# SCH_ESP-Mar_2024-04-21.net
KiCad netlist of a schematic drawn in EasyEDA
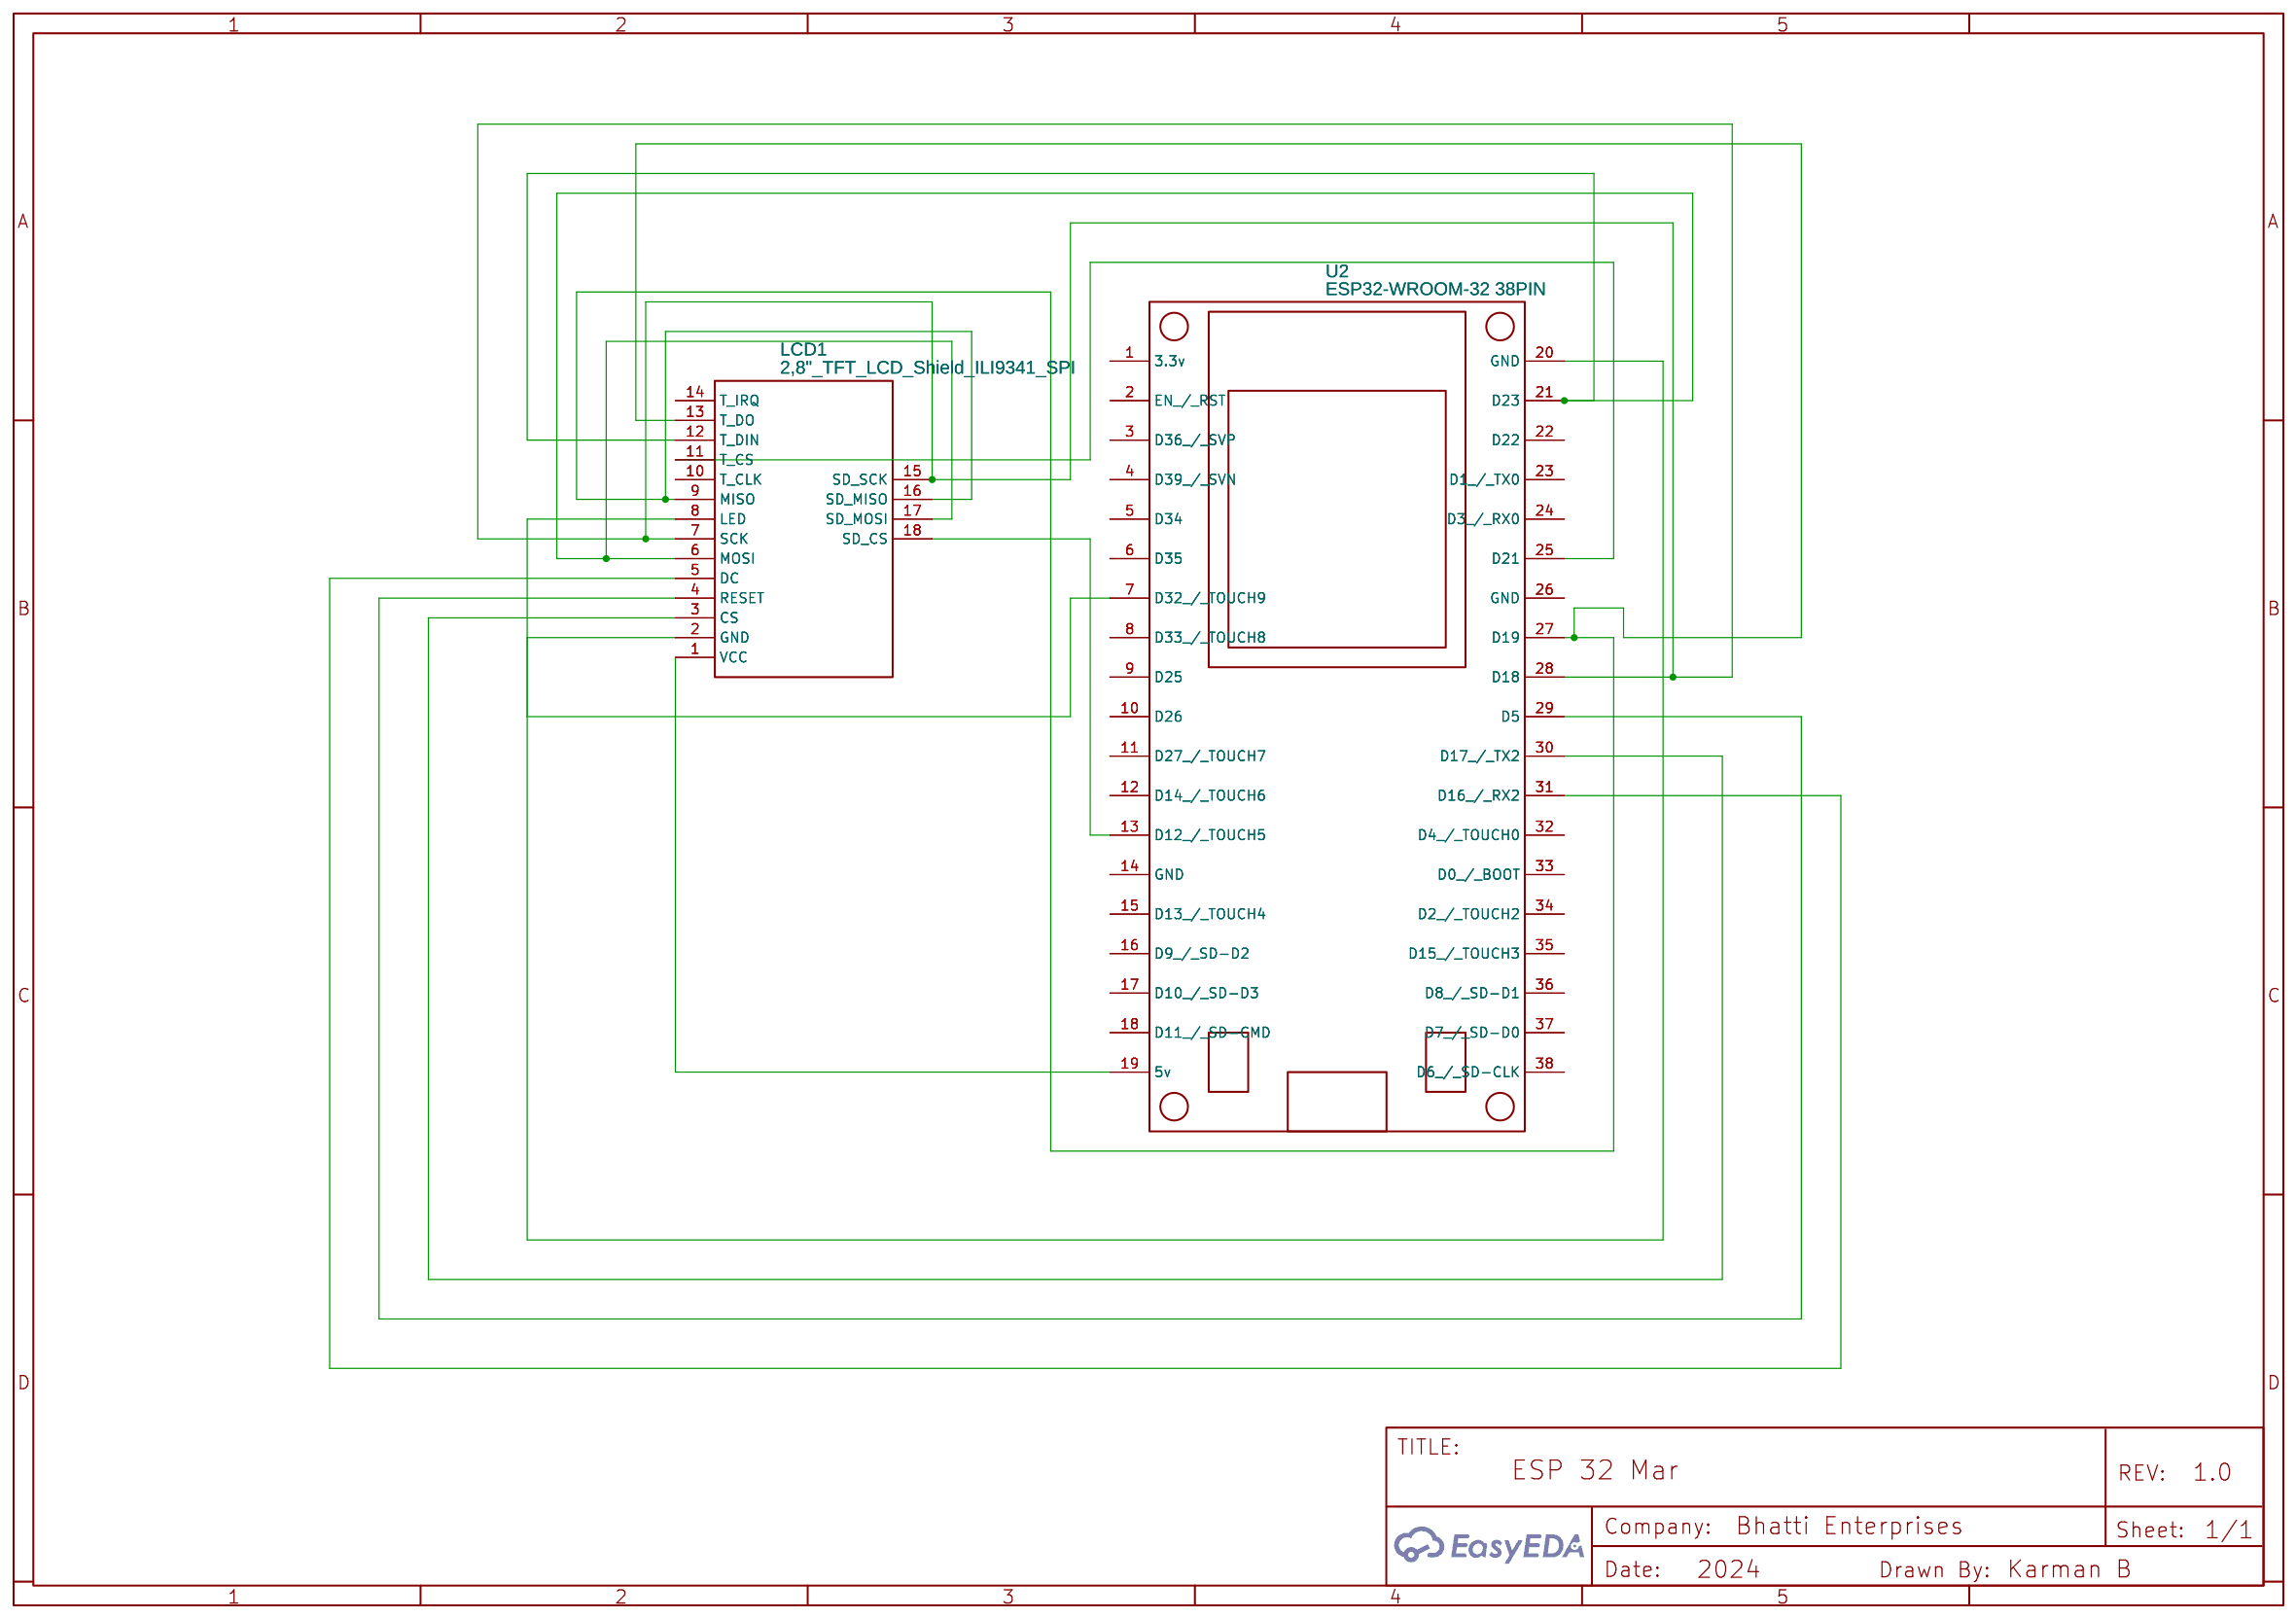
[diagram p0: Sheet_1]
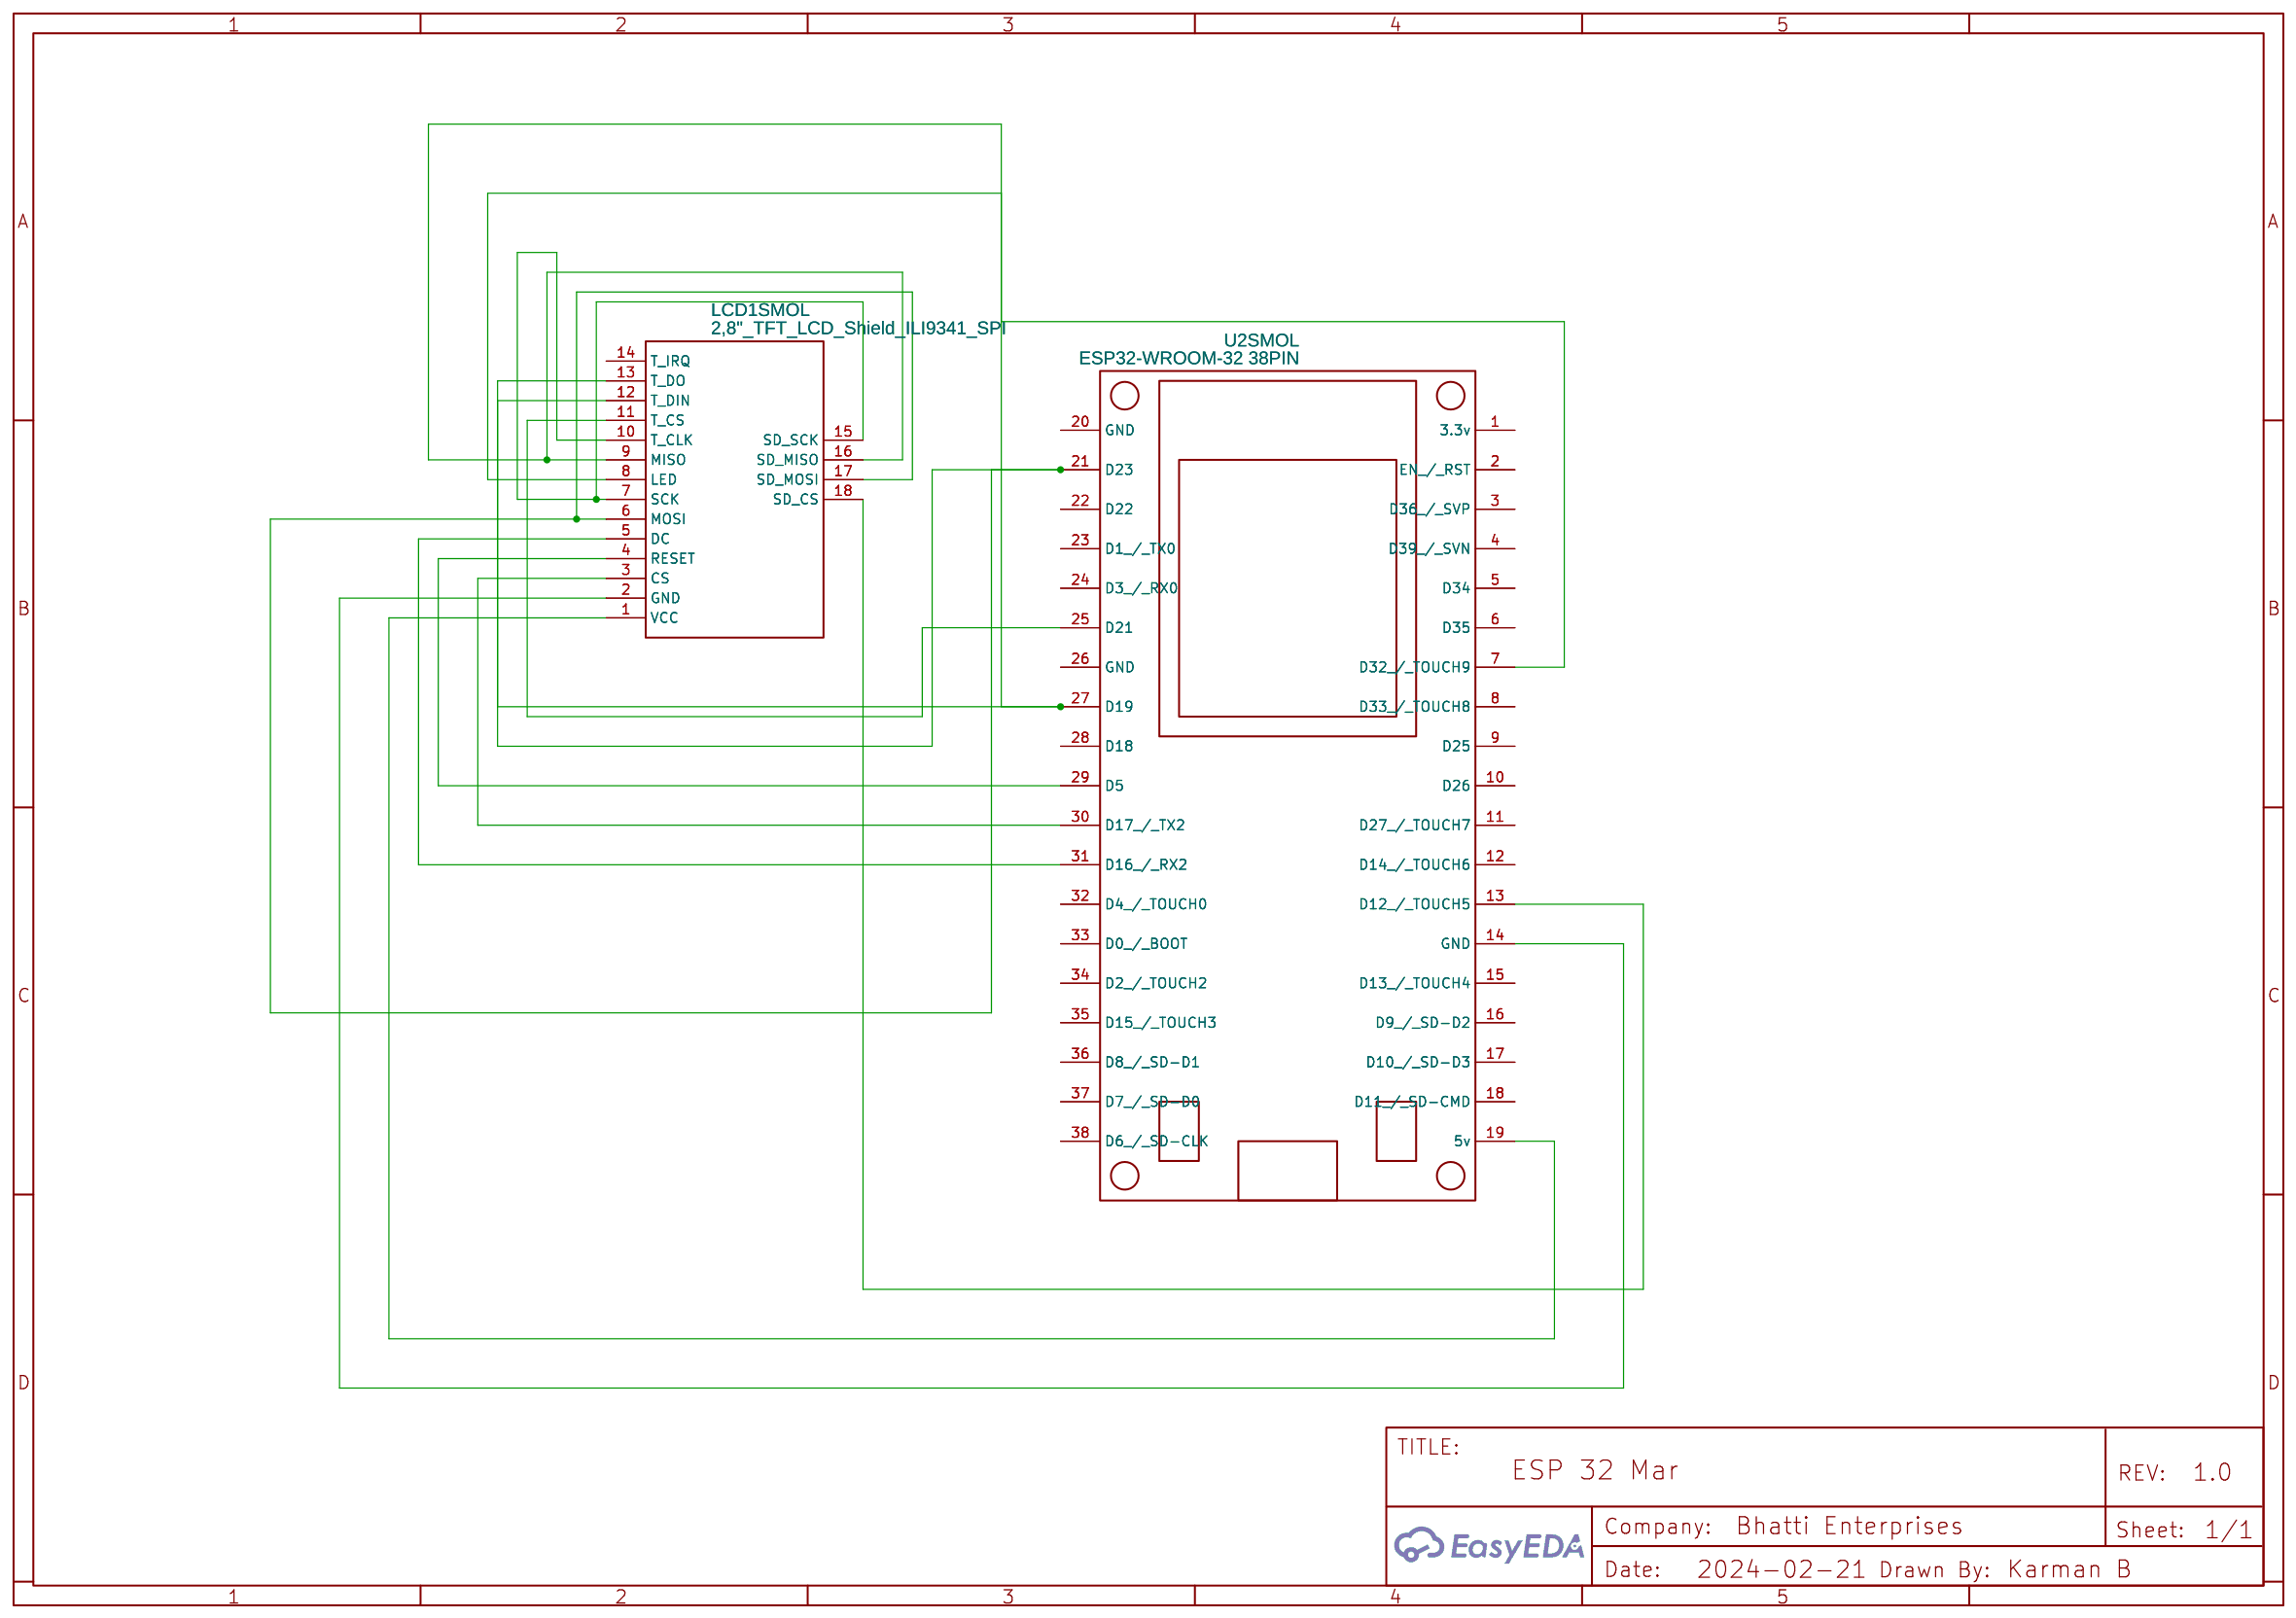
[diagram p1: Sheet SMOL]

(export (version "E")
  (design (tool "Eeschema 10.0.6"))
  (components
    (comp (ref "LCD1")
      (value "2,8\"_TFT_LCD_Shield_ILI9341_SPI")
      (libsource (lib "") (part "2,8{dblquote}_TFT_LCD_Shield_ILI9341_SPI"))
    )
    (comp (ref "U2")
      (value "ESP32-WROOM-32 38PIN")
      (fields (field (name "Manufacturer Part") "ESP32 Development Board"))
      (libsource (lib "") (part "ESP32-WROOM-32 38PIN"))
    )
    (comp (ref "LCD1SMOL")
      (value "2,8\"_TFT_LCD_Shield_ILI9341_SPI")
      (libsource (lib "") (part "2,8{dblquote}_TFT_LCD_Shield_ILI9341_SPI"))
    )
    (comp (ref "U2SMOL")
      (value "ESP32-WROOM-32 38PIN")
      (fields (field (name "Manufacturer Part") "ESP32 Development Board"))
      (libsource (lib "") (part "ESP32-WROOM-32 38PIN"))
    )
  )
  (nets
    (net (code "1") (name "Net-(LCD1-CS)") (class "Default")
      (node (ref "LCD1") (pin "3") (pinfunction "CS_3") (pintype "unspecified"))
      (node (ref "U2") (pin "30") (pinfunction "D17_/_TX2_30") (pintype "bidirectional"))
    )
    (net (code "2") (name "Net-(LCD1-DC)") (class "Default")
      (node (ref "LCD1") (pin "5") (pinfunction "DC_5") (pintype "unspecified"))
      (node (ref "U2") (pin "31") (pinfunction "D16_/_RX2_31") (pintype "bidirectional"))
    )
    (net (code "3") (name "Net-(LCD1-GND)") (class "Default")
      (node (ref "LCD1") (pin "2") (pinfunction "GND_2") (pintype "unspecified"))
      (node (ref "U2") (pin "20") (pinfunction "GND_20") (pintype "passive"))
    )
    (net (code "4") (name "Net-(LCD1-LED)") (class "Default")
      (node (ref "LCD1") (pin "8") (pinfunction "LED_8") (pintype "unspecified"))
      (node (ref "U2") (pin "7") (pinfunction "D32_/_TOUCH9_7") (pintype "bidirectional"))
    )
    (net (code "5") (name "Net-(LCD1-MISO)") (class "Default")
      (node (ref "LCD1") (pin "13") (pinfunction "T_DO_13") (pintype "unspecified"))
      (node (ref "LCD1") (pin "16") (pinfunction "SD_MISO_16") (pintype "unspecified"))
      (node (ref "LCD1") (pin "9") (pinfunction "MISO_9") (pintype "unspecified"))
      (node (ref "U2") (pin "27") (pinfunction "D19_27") (pintype "bidirectional"))
    )
    (net (code "6") (name "Net-(LCD1-MOSI)") (class "Default")
      (node (ref "LCD1") (pin "12") (pinfunction "T_DIN_12") (pintype "unspecified"))
      (node (ref "LCD1") (pin "17") (pinfunction "SD_MOSI_17") (pintype "unspecified"))
      (node (ref "LCD1") (pin "6") (pinfunction "MOSI_6") (pintype "unspecified"))
      (node (ref "U2") (pin "21") (pinfunction "D23_21") (pintype "bidirectional"))
    )
    (net (code "7") (name "Net-(LCD1-RESET)") (class "Default")
      (node (ref "LCD1") (pin "4") (pinfunction "RESET_4") (pintype "unspecified"))
      (node (ref "U2") (pin "29") (pinfunction "D5_29") (pintype "bidirectional"))
    )
    (net (code "8") (name "Net-(LCD1-SCK)") (class "Default")
      (node (ref "LCD1") (pin "15") (pinfunction "SD_SCK_15") (pintype "unspecified"))
      (node (ref "LCD1") (pin "7") (pinfunction "SCK_7") (pintype "unspecified"))
      (node (ref "U2") (pin "28") (pinfunction "D18_28") (pintype "bidirectional"))
    )
    (net (code "9") (name "Net-(LCD1-SD_CS)") (class "Default")
      (node (ref "LCD1") (pin "18") (pinfunction "SD_CS_18") (pintype "unspecified"))
      (node (ref "U2") (pin "13") (pinfunction "D12_/_TOUCH5_13") (pintype "bidirectional"))
    )
    (net (code "10") (name "Net-(LCD1-T_CS)") (class "Default")
      (node (ref "LCD1") (pin "11") (pinfunction "T_CS_11") (pintype "unspecified"))
      (node (ref "U2") (pin "25") (pinfunction "D21_25") (pintype "bidirectional"))
    )
    (net (code "11") (name "Net-(LCD1-VCC)") (class "Default")
      (node (ref "LCD1") (pin "1") (pinfunction "VCC_1") (pintype "unspecified"))
      (node (ref "U2") (pin "19") (pinfunction "5v_19") (pintype "passive"))
    )
    (net (code "12") (name "Net-(LCD1SMOL-CS)") (class "Default")
      (node (ref "LCD1SMOL") (pin "3") (pinfunction "CS_3") (pintype "unspecified"))
      (node (ref "U2SMOL") (pin "30") (pinfunction "D17_/_TX2_30") (pintype "bidirectional"))
    )
    (net (code "13") (name "Net-(LCD1SMOL-DC)") (class "Default")
      (node (ref "LCD1SMOL") (pin "5") (pinfunction "DC_5") (pintype "unspecified"))
      (node (ref "U2SMOL") (pin "31") (pinfunction "D16_/_RX2_31") (pintype "bidirectional"))
    )
    (net (code "14") (name "Net-(LCD1SMOL-GND)") (class "Default")
      (node (ref "LCD1SMOL") (pin "2") (pinfunction "GND_2") (pintype "unspecified"))
      (node (ref "U2SMOL") (pin "14") (pinfunction "GND_14") (pintype "passive"))
    )
    (net (code "15") (name "Net-(LCD1SMOL-LED)") (class "Default")
      (node (ref "LCD1SMOL") (pin "8") (pinfunction "LED_8") (pintype "unspecified"))
      (node (ref "U2SMOL") (pin "7") (pinfunction "D32_/_TOUCH9_7") (pintype "bidirectional"))
    )
    (net (code "16") (name "Net-(LCD1SMOL-MISO)") (class "Default")
      (node (ref "LCD1SMOL") (pin "13") (pinfunction "T_DO_13") (pintype "unspecified"))
      (node (ref "LCD1SMOL") (pin "16") (pinfunction "SD_MISO_16") (pintype "unspecified"))
      (node (ref "LCD1SMOL") (pin "9") (pinfunction "MISO_9") (pintype "unspecified"))
      (node (ref "U2SMOL") (pin "27") (pinfunction "D19_27") (pintype "bidirectional"))
    )
    (net (code "17") (name "Net-(LCD1SMOL-MOSI)") (class "Default")
      (node (ref "LCD1SMOL") (pin "12") (pinfunction "T_DIN_12") (pintype "unspecified"))
      (node (ref "LCD1SMOL") (pin "17") (pinfunction "SD_MOSI_17") (pintype "unspecified"))
      (node (ref "LCD1SMOL") (pin "6") (pinfunction "MOSI_6") (pintype "unspecified"))
      (node (ref "U2SMOL") (pin "21") (pinfunction "D23_21") (pintype "bidirectional"))
    )
    (net (code "18") (name "Net-(LCD1SMOL-RESET)") (class "Default")
      (node (ref "LCD1SMOL") (pin "4") (pinfunction "RESET_4") (pintype "unspecified"))
      (node (ref "U2SMOL") (pin "29") (pinfunction "D5_29") (pintype "bidirectional"))
    )
    (net (code "19") (name "Net-(LCD1SMOL-SCK)") (class "Default")
      (node (ref "LCD1SMOL") (pin "10") (pinfunction "T_CLK_10") (pintype "unspecified"))
      (node (ref "LCD1SMOL") (pin "15") (pinfunction "SD_SCK_15") (pintype "unspecified"))
      (node (ref "LCD1SMOL") (pin "7") (pinfunction "SCK_7") (pintype "unspecified"))
    )
    (net (code "20") (name "Net-(LCD1SMOL-SD_CS)") (class "Default")
      (node (ref "LCD1SMOL") (pin "18") (pinfunction "SD_CS_18") (pintype "unspecified"))
      (node (ref "U2SMOL") (pin "13") (pinfunction "D12_/_TOUCH5_13") (pintype "bidirectional"))
    )
    (net (code "21") (name "Net-(LCD1SMOL-T_CS)") (class "Default")
      (node (ref "LCD1SMOL") (pin "11") (pinfunction "T_CS_11") (pintype "unspecified"))
      (node (ref "U2SMOL") (pin "25") (pinfunction "D21_25") (pintype "bidirectional"))
    )
    (net (code "22") (name "Net-(LCD1SMOL-VCC)") (class "Default")
      (node (ref "LCD1SMOL") (pin "1") (pinfunction "VCC_1") (pintype "unspecified"))
      (node (ref "U2SMOL") (pin "19") (pinfunction "5v_19") (pintype "passive"))
    )
    (net (code "23") (name "unconnected-(LCD1-T_CLK-Pad10)") (class "Default")
      (node (ref "LCD1") (pin "10") (pinfunction "T_CLK_10") (pintype "unspecified"))
    )
    (net (code "24") (name "unconnected-(LCD1-T_IRQ-Pad14)") (class "Default")
      (node (ref "LCD1") (pin "14") (pinfunction "T_IRQ_14") (pintype "unspecified"))
    )
    (net (code "25") (name "unconnected-(LCD1SMOL-T_IRQ-Pad14)") (class "Default")
      (node (ref "LCD1SMOL") (pin "14") (pinfunction "T_IRQ_14") (pintype "unspecified"))
    )
    (net (code "26") (name "unconnected-(U2-3.3v-Pad1)") (class "Default")
      (node (ref "U2") (pin "1") (pinfunction "3.3v_1") (pintype "passive"))
    )
    (net (code "27") (name "unconnected-(U2-D0_{slash}_BOOT-Pad33)") (class "Default")
      (node (ref "U2") (pin "33") (pinfunction "D0_/_BOOT_33") (pintype "bidirectional"))
    )
    (net (code "28") (name "unconnected-(U2-D1_{slash}_TX0-Pad23)") (class "Default")
      (node (ref "U2") (pin "23") (pinfunction "D1_/_TX0_23") (pintype "bidirectional"))
    )
    (net (code "29") (name "unconnected-(U2-D2_{slash}_TOUCH2-Pad34)") (class "Default")
      (node (ref "U2") (pin "34") (pinfunction "D2_/_TOUCH2_34") (pintype "bidirectional"))
    )
    (net (code "30") (name "unconnected-(U2-D3_{slash}_RX0-Pad24)") (class "Default")
      (node (ref "U2") (pin "24") (pinfunction "D3_/_RX0_24") (pintype "bidirectional"))
    )
    (net (code "31") (name "unconnected-(U2-D4_{slash}_TOUCH0-Pad32)") (class "Default")
      (node (ref "U2") (pin "32") (pinfunction "D4_/_TOUCH0_32") (pintype "bidirectional"))
    )
    (net (code "32") (name "unconnected-(U2-D6_{slash}_SD-CLK-Pad38)") (class "Default")
      (node (ref "U2") (pin "38") (pinfunction "D6_/_SD-CLK_38") (pintype "bidirectional"))
    )
    (net (code "33") (name "unconnected-(U2-D7_{slash}_SD-D0-Pad37)") (class "Default")
      (node (ref "U2") (pin "37") (pinfunction "D7_/_SD-D0_37") (pintype "bidirectional"))
    )
    (net (code "34") (name "unconnected-(U2-D8_{slash}_SD-D1-Pad36)") (class "Default")
      (node (ref "U2") (pin "36") (pinfunction "D8_/_SD-D1_36") (pintype "bidirectional"))
    )
    (net (code "35") (name "unconnected-(U2-D9_{slash}_SD-D2-Pad16)") (class "Default")
      (node (ref "U2") (pin "16") (pinfunction "D9_/_SD-D2_16") (pintype "bidirectional"))
    )
    (net (code "36") (name "unconnected-(U2-D10_{slash}_SD-D3-Pad17)") (class "Default")
      (node (ref "U2") (pin "17") (pinfunction "D10_/_SD-D3_17") (pintype "bidirectional"))
    )
    (net (code "37") (name "unconnected-(U2-D11_{slash}_SD-CMD-Pad18)") (class "Default")
      (node (ref "U2") (pin "18") (pinfunction "D11_/_SD-CMD_18") (pintype "bidirectional"))
    )
    (net (code "38") (name "unconnected-(U2-D13_{slash}_TOUCH4-Pad15)") (class "Default")
      (node (ref "U2") (pin "15") (pinfunction "D13_/_TOUCH4_15") (pintype "bidirectional"))
    )
    (net (code "39") (name "unconnected-(U2-D14_{slash}_TOUCH6-Pad12)") (class "Default")
      (node (ref "U2") (pin "12") (pinfunction "D14_/_TOUCH6_12") (pintype "bidirectional"))
    )
    (net (code "40") (name "unconnected-(U2-D15_{slash}_TOUCH3-Pad35)") (class "Default")
      (node (ref "U2") (pin "35") (pinfunction "D15_/_TOUCH3_35") (pintype "bidirectional"))
    )
    (net (code "41") (name "unconnected-(U2-D22-Pad22)") (class "Default")
      (node (ref "U2") (pin "22") (pinfunction "D22_22") (pintype "bidirectional"))
    )
    (net (code "42") (name "unconnected-(U2-D25-Pad9)") (class "Default")
      (node (ref "U2") (pin "9") (pinfunction "D25_9") (pintype "bidirectional"))
    )
    (net (code "43") (name "unconnected-(U2-D26-Pad10)") (class "Default")
      (node (ref "U2") (pin "10") (pinfunction "D26_10") (pintype "bidirectional"))
    )
    (net (code "44") (name "unconnected-(U2-D27_{slash}_TOUCH7-Pad11)") (class "Default")
      (node (ref "U2") (pin "11") (pinfunction "D27_/_TOUCH7_11") (pintype "bidirectional"))
    )
    (net (code "45") (name "unconnected-(U2-D33_{slash}_TOUCH8-Pad8)") (class "Default")
      (node (ref "U2") (pin "8") (pinfunction "D33_/_TOUCH8_8") (pintype "bidirectional"))
    )
    (net (code "46") (name "unconnected-(U2-D34-Pad5)") (class "Default")
      (node (ref "U2") (pin "5") (pinfunction "D34_5") (pintype "bidirectional"))
    )
    (net (code "47") (name "unconnected-(U2-D35-Pad6)") (class "Default")
      (node (ref "U2") (pin "6") (pinfunction "D35_6") (pintype "bidirectional"))
    )
    (net (code "48") (name "unconnected-(U2-D36_{slash}_SVP-Pad3)") (class "Default")
      (node (ref "U2") (pin "3") (pinfunction "D36_/_SVP_3") (pintype "bidirectional"))
    )
    (net (code "49") (name "unconnected-(U2-D39_{slash}_SVN-Pad4)") (class "Default")
      (node (ref "U2") (pin "4") (pinfunction "D39_/_SVN_4") (pintype "bidirectional"))
    )
    (net (code "50") (name "unconnected-(U2-EN_{slash}_RST-Pad2)") (class "Default")
      (node (ref "U2") (pin "2") (pinfunction "EN_/_RST_2") (pintype "bidirectional"))
    )
    (net (code "51") (name "unconnected-(U2-GND-Pad14)") (class "Default")
      (node (ref "U2") (pin "14") (pinfunction "GND_14") (pintype "passive"))
    )
    (net (code "52") (name "unconnected-(U2-GND-Pad26)") (class "Default")
      (node (ref "U2") (pin "26") (pinfunction "GND_26") (pintype "passive"))
    )
    (net (code "53") (name "unconnected-(U2SMOL-3.3v-Pad1)") (class "Default")
      (node (ref "U2SMOL") (pin "1") (pinfunction "3.3v_1") (pintype "passive"))
    )
    (net (code "54") (name "unconnected-(U2SMOL-D0_{slash}_BOOT-Pad33)") (class "Default")
      (node (ref "U2SMOL") (pin "33") (pinfunction "D0_/_BOOT_33") (pintype "bidirectional"))
    )
    (net (code "55") (name "unconnected-(U2SMOL-D1_{slash}_TX0-Pad23)") (class "Default")
      (node (ref "U2SMOL") (pin "23") (pinfunction "D1_/_TX0_23") (pintype "bidirectional"))
    )
    (net (code "56") (name "unconnected-(U2SMOL-D2_{slash}_TOUCH2-Pad34)") (class "Default")
      (node (ref "U2SMOL") (pin "34") (pinfunction "D2_/_TOUCH2_34") (pintype "bidirectional"))
    )
    (net (code "57") (name "unconnected-(U2SMOL-D3_{slash}_RX0-Pad24)") (class "Default")
      (node (ref "U2SMOL") (pin "24") (pinfunction "D3_/_RX0_24") (pintype "bidirectional"))
    )
    (net (code "58") (name "unconnected-(U2SMOL-D4_{slash}_TOUCH0-Pad32)") (class "Default")
      (node (ref "U2SMOL") (pin "32") (pinfunction "D4_/_TOUCH0_32") (pintype "bidirectional"))
    )
    (net (code "59") (name "unconnected-(U2SMOL-D6_{slash}_SD-CLK-Pad38)") (class "Default")
      (node (ref "U2SMOL") (pin "38") (pinfunction "D6_/_SD-CLK_38") (pintype "bidirectional"))
    )
    (net (code "60") (name "unconnected-(U2SMOL-D7_{slash}_SD-D0-Pad37)") (class "Default")
      (node (ref "U2SMOL") (pin "37") (pinfunction "D7_/_SD-D0_37") (pintype "bidirectional"))
    )
    (net (code "61") (name "unconnected-(U2SMOL-D8_{slash}_SD-D1-Pad36)") (class "Default")
      (node (ref "U2SMOL") (pin "36") (pinfunction "D8_/_SD-D1_36") (pintype "bidirectional"))
    )
    (net (code "62") (name "unconnected-(U2SMOL-D9_{slash}_SD-D2-Pad16)") (class "Default")
      (node (ref "U2SMOL") (pin "16") (pinfunction "D9_/_SD-D2_16") (pintype "bidirectional"))
    )
    (net (code "63") (name "unconnected-(U2SMOL-D10_{slash}_SD-D3-Pad17)") (class "Default")
      (node (ref "U2SMOL") (pin "17") (pinfunction "D10_/_SD-D3_17") (pintype "bidirectional"))
    )
    (net (code "64") (name "unconnected-(U2SMOL-D11_{slash}_SD-CMD-Pad18)") (class "Default")
      (node (ref "U2SMOL") (pin "18") (pinfunction "D11_/_SD-CMD_18") (pintype "bidirectional"))
    )
    (net (code "65") (name "unconnected-(U2SMOL-D13_{slash}_TOUCH4-Pad15)") (class "Default")
      (node (ref "U2SMOL") (pin "15") (pinfunction "D13_/_TOUCH4_15") (pintype "bidirectional"))
    )
    (net (code "66") (name "unconnected-(U2SMOL-D14_{slash}_TOUCH6-Pad12)") (class "Default")
      (node (ref "U2SMOL") (pin "12") (pinfunction "D14_/_TOUCH6_12") (pintype "bidirectional"))
    )
    (net (code "67") (name "unconnected-(U2SMOL-D15_{slash}_TOUCH3-Pad35)") (class "Default")
      (node (ref "U2SMOL") (pin "35") (pinfunction "D15_/_TOUCH3_35") (pintype "bidirectional"))
    )
    (net (code "68") (name "unconnected-(U2SMOL-D18-Pad28)") (class "Default")
      (node (ref "U2SMOL") (pin "28") (pinfunction "D18_28") (pintype "bidirectional"))
    )
    (net (code "69") (name "unconnected-(U2SMOL-D22-Pad22)") (class "Default")
      (node (ref "U2SMOL") (pin "22") (pinfunction "D22_22") (pintype "bidirectional"))
    )
    (net (code "70") (name "unconnected-(U2SMOL-D25-Pad9)") (class "Default")
      (node (ref "U2SMOL") (pin "9") (pinfunction "D25_9") (pintype "bidirectional"))
    )
    (net (code "71") (name "unconnected-(U2SMOL-D26-Pad10)") (class "Default")
      (node (ref "U2SMOL") (pin "10") (pinfunction "D26_10") (pintype "bidirectional"))
    )
    (net (code "72") (name "unconnected-(U2SMOL-D27_{slash}_TOUCH7-Pad11)") (class "Default")
      (node (ref "U2SMOL") (pin "11") (pinfunction "D27_/_TOUCH7_11") (pintype "bidirectional"))
    )
    (net (code "73") (name "unconnected-(U2SMOL-D33_{slash}_TOUCH8-Pad8)") (class "Default")
      (node (ref "U2SMOL") (pin "8") (pinfunction "D33_/_TOUCH8_8") (pintype "bidirectional"))
    )
    (net (code "74") (name "unconnected-(U2SMOL-D34-Pad5)") (class "Default")
      (node (ref "U2SMOL") (pin "5") (pinfunction "D34_5") (pintype "bidirectional"))
    )
    (net (code "75") (name "unconnected-(U2SMOL-D35-Pad6)") (class "Default")
      (node (ref "U2SMOL") (pin "6") (pinfunction "D35_6") (pintype "bidirectional"))
    )
    (net (code "76") (name "unconnected-(U2SMOL-D36_{slash}_SVP-Pad3)") (class "Default")
      (node (ref "U2SMOL") (pin "3") (pinfunction "D36_/_SVP_3") (pintype "bidirectional"))
    )
    (net (code "77") (name "unconnected-(U2SMOL-D39_{slash}_SVN-Pad4)") (class "Default")
      (node (ref "U2SMOL") (pin "4") (pinfunction "D39_/_SVN_4") (pintype "bidirectional"))
    )
    (net (code "78") (name "unconnected-(U2SMOL-EN_{slash}_RST-Pad2)") (class "Default")
      (node (ref "U2SMOL") (pin "2") (pinfunction "EN_/_RST_2") (pintype "bidirectional"))
    )
    (net (code "79") (name "unconnected-(U2SMOL-GND-Pad20)") (class "Default")
      (node (ref "U2SMOL") (pin "20") (pinfunction "GND_20") (pintype "passive"))
    )
    (net (code "80") (name "unconnected-(U2SMOL-GND-Pad26)") (class "Default")
      (node (ref "U2SMOL") (pin "26") (pinfunction "GND_26") (pintype "passive"))
    )
  )
)
